# esp12_shield.net
KiCad netlist of a schematic drawn in EAGLE
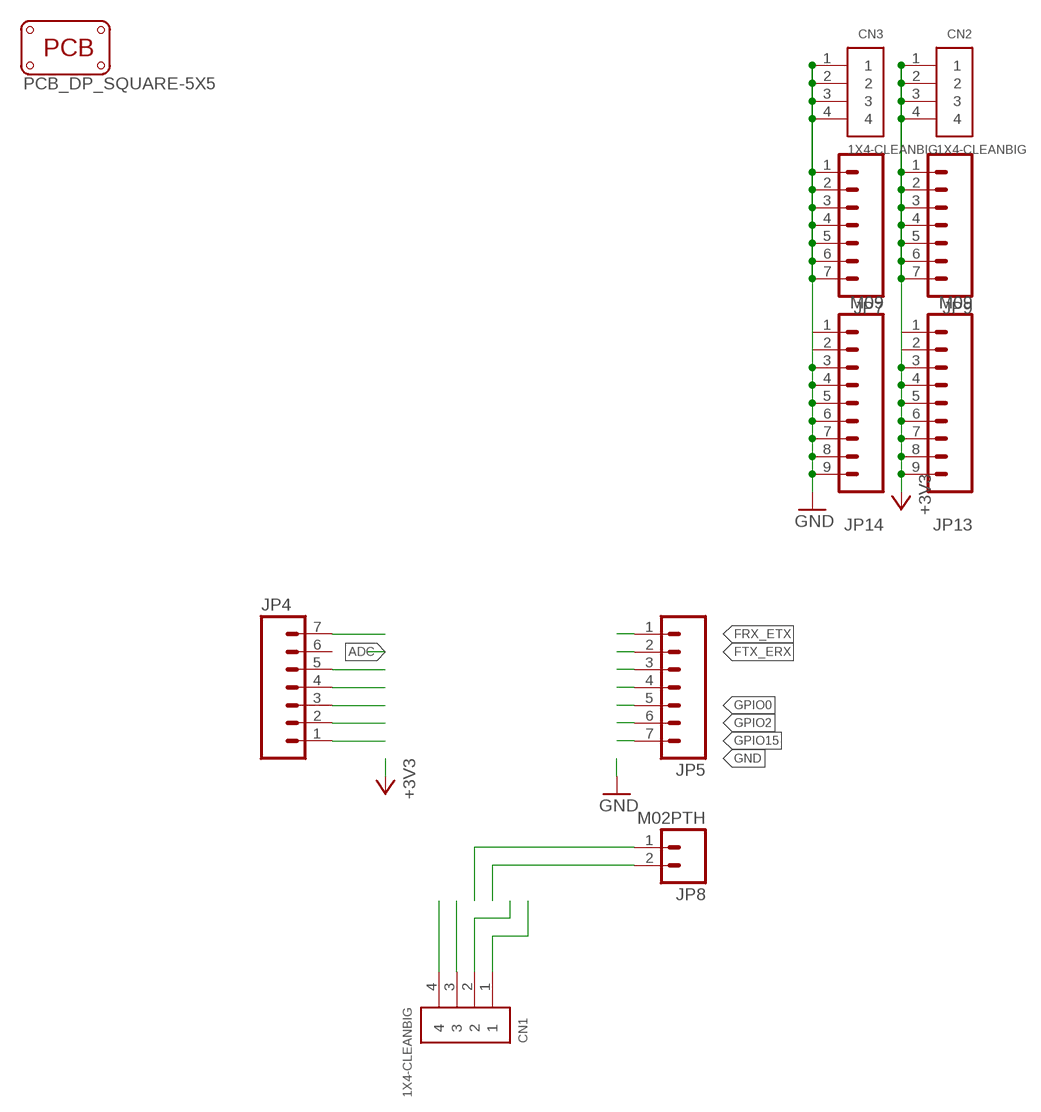
[diagram p0: schematic, sheet 1]

(export (version "E")
  (design (tool "Eeschema 10.0.6"))
  (components
    (comp (ref "CN1")
      (value "1X4-CLEANBIG")
      (footprint "eagle-import:1X04-CLEANBIG")
      (libsource (lib "eagle-import") (part "1X4-CLEANBIG"))
    )
    (comp (ref "CN2")
      (value "1X4-CLEANBIG")
      (footprint "eagle-import:1X04-CLEANBIG")
      (libsource (lib "eagle-import") (part "1X4-CLEANBIG"))
    )
    (comp (ref "CN3")
      (value "1X4-CLEANBIG")
      (footprint "eagle-import:1X04-CLEANBIG")
      (libsource (lib "eagle-import") (part "1X4-CLEANBIG"))
    )
    (comp (ref "JP4")
      (value "M07")
      (footprint "eagle-import:1X07")
      (libsource (lib "eagle-import") (part "M07"))
    )
    (comp (ref "JP5")
      (value "M07")
      (footprint "eagle-import:1X07")
      (libsource (lib "eagle-import") (part "M07"))
    )
    (comp (ref "JP7")
      (value "M07")
      (footprint "eagle-import:1X07")
      (libsource (lib "eagle-import") (part "M07"))
    )
    (comp (ref "JP8")
      (value "M02PTH")
      (footprint "eagle-import:1X02")
      (libsource (lib "eagle-import") (part "M02PTH"))
    )
    (comp (ref "JP9")
      (value "M07")
      (footprint "eagle-import:1X07")
      (libsource (lib "eagle-import") (part "M07"))
    )
    (comp (ref "JP13")
      (value "M09")
      (footprint "eagle-import:1X09")
      (libsource (lib "eagle-import") (part "M09"))
    )
    (comp (ref "JP14")
      (value "M09")
      (footprint "eagle-import:1X09")
      (libsource (lib "eagle-import") (part "M09"))
    )
    (comp (ref "PCB1")
      (value "PCB_DP_SQUARE-5X5")
      (footprint "eagle-import:DP5050_V1")
      (libsource (lib "eagle-import") (part "PCB_DP_SQUARE-5X5"))
    )
  )
  (nets
    (net (code "1") (name "+3V3") (class "Default")
      (node (ref "CN2") (pin "1") (pinfunction "1_1") (pintype "bidirectional"))
      (node (ref "CN2") (pin "2") (pinfunction "2_2") (pintype "bidirectional"))
      (node (ref "CN2") (pin "3") (pinfunction "3_3") (pintype "bidirectional"))
      (node (ref "CN2") (pin "4") (pinfunction "4_4") (pintype "bidirectional"))
      (node (ref "JP13") (pin "1") (pinfunction "1_1") (pintype "passive"))
      (node (ref "JP13") (pin "2") (pinfunction "2_2") (pintype "passive"))
      (node (ref "JP13") (pin "3") (pinfunction "3_3") (pintype "passive"))
      (node (ref "JP13") (pin "4") (pinfunction "4_4") (pintype "passive"))
      (node (ref "JP13") (pin "5") (pinfunction "5_5") (pintype "passive"))
      (node (ref "JP13") (pin "6") (pinfunction "6_6") (pintype "passive"))
      (node (ref "JP13") (pin "7") (pinfunction "7_7") (pintype "passive"))
      (node (ref "JP13") (pin "8") (pinfunction "8_8") (pintype "passive"))
      (node (ref "JP13") (pin "9") (pinfunction "9_9") (pintype "passive"))
      (node (ref "JP9") (pin "1") (pinfunction "1_1") (pintype "passive"))
      (node (ref "JP9") (pin "2") (pinfunction "2_2") (pintype "passive"))
      (node (ref "JP9") (pin "3") (pinfunction "3_3") (pintype "passive"))
      (node (ref "JP9") (pin "4") (pinfunction "4_4") (pintype "passive"))
      (node (ref "JP9") (pin "5") (pinfunction "5_5") (pintype "passive"))
      (node (ref "JP9") (pin "6") (pinfunction "6_6") (pintype "passive"))
      (node (ref "JP9") (pin "7") (pinfunction "7_7") (pintype "passive"))
    )
    (net (code "3") (name "FRX_ETX") (class "Default")
      (node (ref "JP5") (pin "1") (pinfunction "1_1") (pintype "passive"))
    )
    (net (code "4") (name "FTX_ERX") (class "Default")
      (node (ref "JP5") (pin "2") (pinfunction "2_2") (pintype "passive"))
    )
    (net (code "5") (name "GND") (class "Default")
      (node (ref "CN3") (pin "1") (pinfunction "1_1") (pintype "bidirectional"))
      (node (ref "CN3") (pin "2") (pinfunction "2_2") (pintype "bidirectional"))
      (node (ref "CN3") (pin "3") (pinfunction "3_3") (pintype "bidirectional"))
      (node (ref "CN3") (pin "4") (pinfunction "4_4") (pintype "bidirectional"))
      (node (ref "JP14") (pin "1") (pinfunction "1_1") (pintype "passive"))
      (node (ref "JP14") (pin "2") (pinfunction "2_2") (pintype "passive"))
      (node (ref "JP14") (pin "3") (pinfunction "3_3") (pintype "passive"))
      (node (ref "JP14") (pin "4") (pinfunction "4_4") (pintype "passive"))
      (node (ref "JP14") (pin "5") (pinfunction "5_5") (pintype "passive"))
      (node (ref "JP14") (pin "6") (pinfunction "6_6") (pintype "passive"))
      (node (ref "JP14") (pin "7") (pinfunction "7_7") (pintype "passive"))
      (node (ref "JP14") (pin "8") (pinfunction "8_8") (pintype "passive"))
      (node (ref "JP14") (pin "9") (pinfunction "9_9") (pintype "passive"))
      (node (ref "JP7") (pin "1") (pinfunction "1_1") (pintype "passive"))
      (node (ref "JP7") (pin "2") (pinfunction "2_2") (pintype "passive"))
      (node (ref "JP7") (pin "3") (pinfunction "3_3") (pintype "passive"))
      (node (ref "JP7") (pin "4") (pinfunction "4_4") (pintype "passive"))
      (node (ref "JP7") (pin "5") (pinfunction "5_5") (pintype "passive"))
      (node (ref "JP7") (pin "6") (pinfunction "6_6") (pintype "passive"))
      (node (ref "JP7") (pin "7") (pinfunction "7_7") (pintype "passive"))
    )
    (net (code "6") (name "GPIO0") (class "Default")
      (node (ref "JP5") (pin "5") (pinfunction "5_5") (pintype "passive"))
    )
    (net (code "7") (name "GPIO2") (class "Default")
      (node (ref "JP5") (pin "6") (pinfunction "6_6") (pintype "passive"))
    )
    (net (code "8") (name "GPIO15") (class "Default")
      (node (ref "JP5") (pin "7") (pinfunction "7_7") (pintype "passive"))
    )
    (net (code "9") (name "unconnected-(CN1-Pad1)") (class "Default")
      (node (ref "CN1") (pin "1") (pinfunction "1_1") (pintype "bidirectional"))
    )
    (net (code "10") (name "unconnected-(CN1-Pad2)") (class "Default")
      (node (ref "CN1") (pin "2") (pinfunction "2_2") (pintype "bidirectional"))
    )
    (net (code "11") (name "unconnected-(CN1-Pad3)") (class "Default")
      (node (ref "CN1") (pin "3") (pinfunction "3_3") (pintype "bidirectional"))
    )
    (net (code "12") (name "unconnected-(CN1-Pad4)") (class "Default")
      (node (ref "CN1") (pin "4") (pinfunction "4_4") (pintype "bidirectional"))
    )
    (net (code "13") (name "unconnected-(JP4-Pad1)") (class "Default")
      (node (ref "JP4") (pin "1") (pinfunction "1_1") (pintype "passive"))
    )
    (net (code "14") (name "unconnected-(JP4-Pad2)") (class "Default")
      (node (ref "JP4") (pin "2") (pinfunction "2_2") (pintype "passive"))
    )
    (net (code "15") (name "unconnected-(JP4-Pad3)") (class "Default")
      (node (ref "JP4") (pin "3") (pinfunction "3_3") (pintype "passive"))
    )
    (net (code "16") (name "unconnected-(JP4-Pad4)") (class "Default")
      (node (ref "JP4") (pin "4") (pinfunction "4_4") (pintype "passive"))
    )
    (net (code "17") (name "unconnected-(JP4-Pad5)") (class "Default")
      (node (ref "JP4") (pin "5") (pinfunction "5_5") (pintype "passive"))
    )
    (net (code "18") (name "unconnected-(JP4-Pad6)") (class "Default")
      (node (ref "JP4") (pin "6") (pinfunction "6_6") (pintype "passive"))
    )
    (net (code "19") (name "unconnected-(JP4-Pad7)") (class "Default")
      (node (ref "JP4") (pin "7") (pinfunction "7_7") (pintype "passive"))
    )
    (net (code "20") (name "unconnected-(JP5-Pad3)") (class "Default")
      (node (ref "JP5") (pin "3") (pinfunction "3_3") (pintype "passive"))
    )
    (net (code "21") (name "unconnected-(JP5-Pad4)") (class "Default")
      (node (ref "JP5") (pin "4") (pinfunction "4_4") (pintype "passive"))
    )
    (net (code "22") (name "unconnected-(JP8-Pad1)") (class "Default")
      (node (ref "JP8") (pin "1") (pinfunction "1_1") (pintype "passive"))
    )
    (net (code "23") (name "unconnected-(JP8-Pad2)") (class "Default")
      (node (ref "JP8") (pin "2") (pinfunction "2_2") (pintype "passive"))
    )
  )
)
